# 0118-LEDz.net
KiCad netlist of a schematic drawn in EAGLE
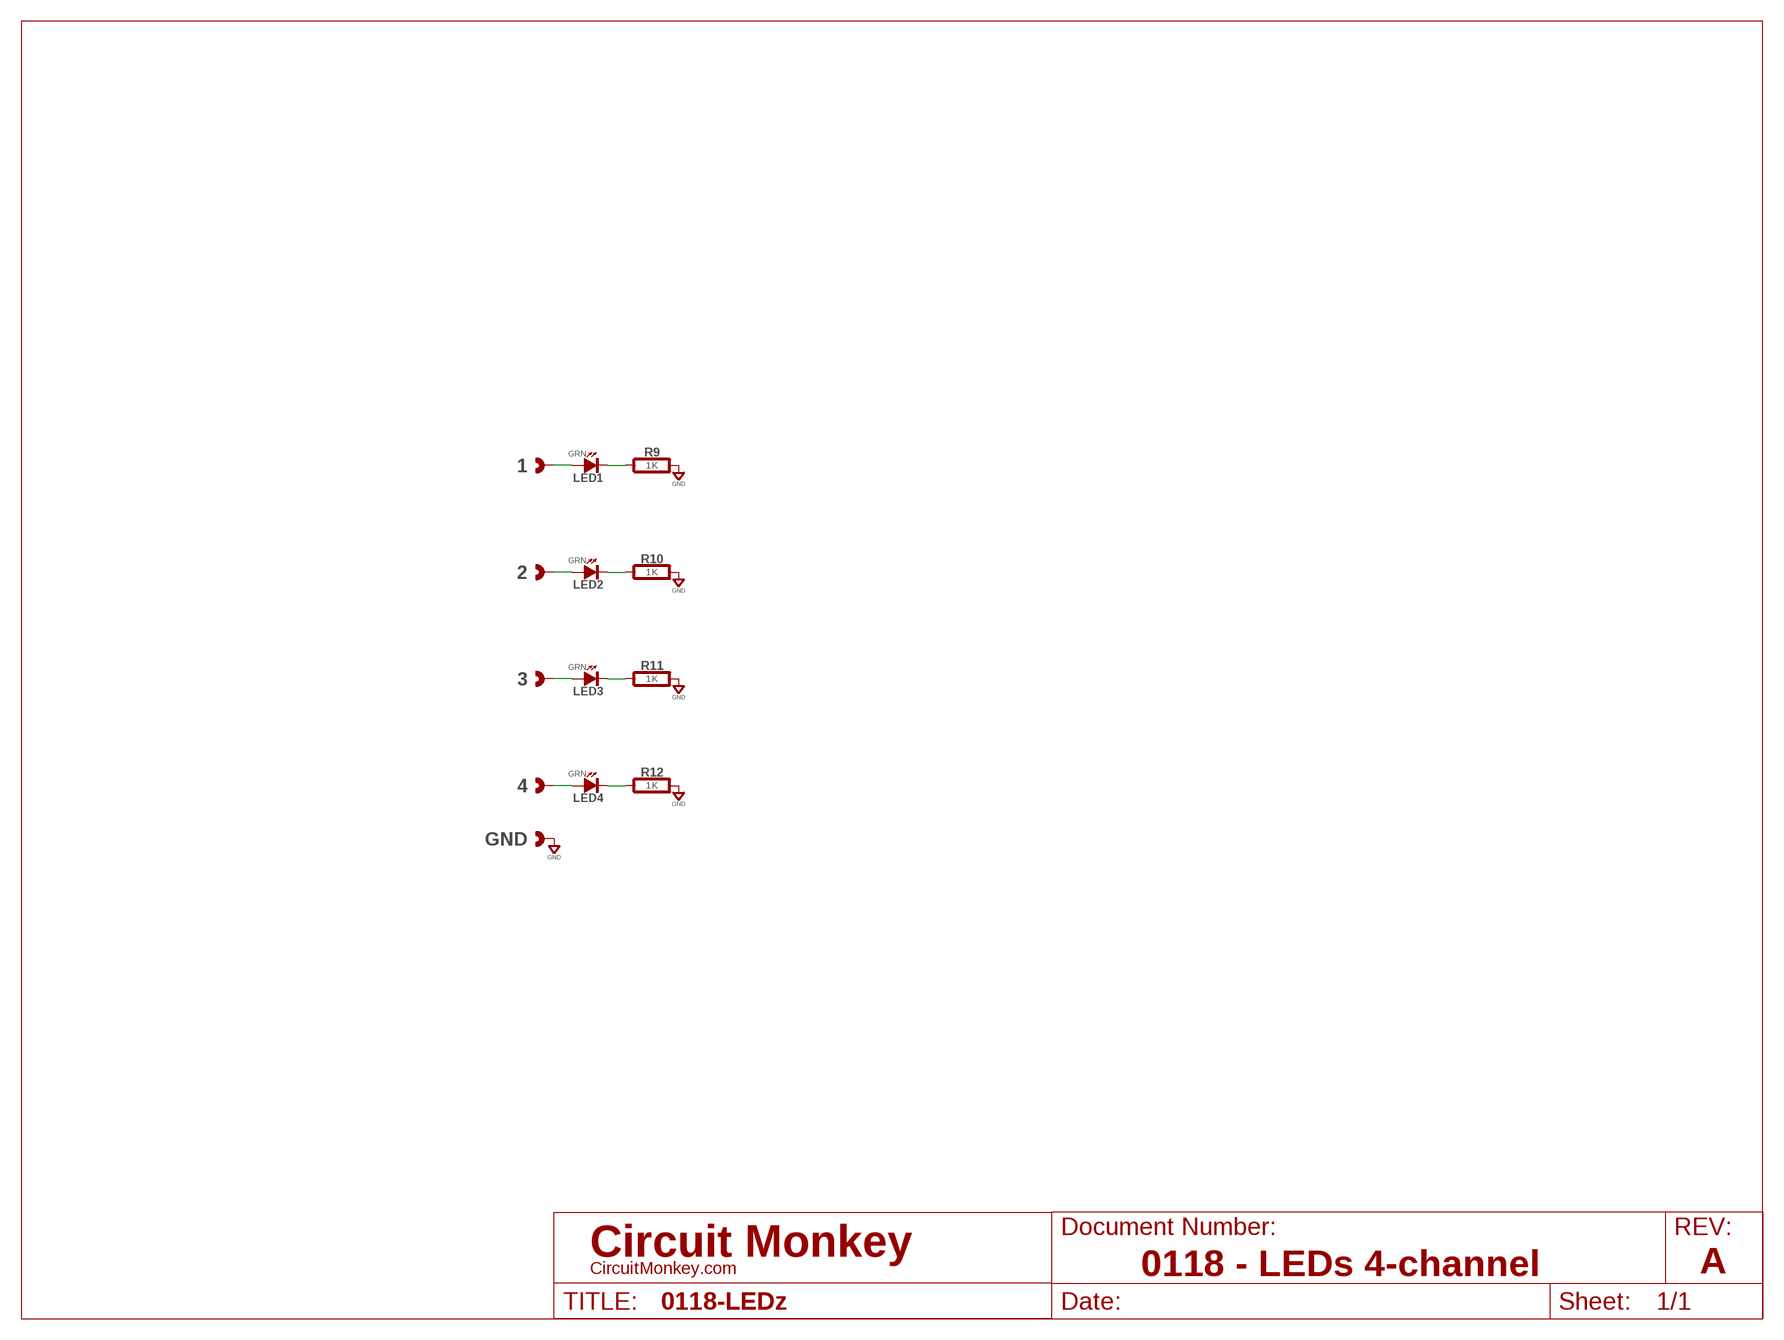
[diagram p0: schematic, sheet 1]

(export (version "E")
  (design (tool "Eeschema 10.0.6"))
  (components
    (comp (ref "1")
      (value "CAST-01X12.00MM")
      (footprint "eagle-import:CAST01-2.00MM")
      (libsource (lib "eagle-import") (part "CAST-01X12.00MM"))
    )
    (comp (ref "2")
      (value "CAST-01X12.00MM")
      (footprint "eagle-import:CAST01-2.00MM")
      (libsource (lib "eagle-import") (part "CAST-01X12.00MM"))
    )
    (comp (ref "3")
      (value "CAST-01X12.00MM")
      (footprint "eagle-import:CAST01-2.00MM")
      (libsource (lib "eagle-import") (part "CAST-01X12.00MM"))
    )
    (comp (ref "4")
      (value "CAST-01X12.00MM")
      (footprint "eagle-import:CAST01-2.00MM")
      (libsource (lib "eagle-import") (part "CAST-01X12.00MM"))
    )
    (comp (ref "GND")
      (value "CAST-01X12.00MM")
      (footprint "eagle-import:CAST01-2.00MM")
      (libsource (lib "eagle-import") (part "CAST-01X12.00MM"))
    )
    (comp (ref "LED1")
      (value "GRN")
      (footprint "eagle-import:SMD_0603")
      (libsource (lib "eagle-import") (part "SMT0603"))
    )
    (comp (ref "LED2")
      (value "GRN")
      (footprint "eagle-import:SMD_0603")
      (libsource (lib "eagle-import") (part "SMT0603"))
    )
    (comp (ref "LED3")
      (value "GRN")
      (footprint "eagle-import:SMD_0603")
      (libsource (lib "eagle-import") (part "SMT0603"))
    )
    (comp (ref "LED4")
      (value "GRN")
      (footprint "eagle-import:SMD_0603")
      (libsource (lib "eagle-import") (part "SMT0603"))
    )
    (comp (ref "R9")
      (value "1K")
      (footprint "eagle-import:0603-RES")
      (libsource (lib "eagle-import") (part "RESISTOR0603"))
    )
    (comp (ref "R10")
      (value "1K")
      (footprint "eagle-import:0603-RES")
      (libsource (lib "eagle-import") (part "RESISTOR0603"))
    )
    (comp (ref "R11")
      (value "1K")
      (footprint "eagle-import:0603-RES")
      (libsource (lib "eagle-import") (part "RESISTOR0603"))
    )
    (comp (ref "R12")
      (value "1K")
      (footprint "eagle-import:0603-RES")
      (libsource (lib "eagle-import") (part "RESISTOR0603"))
    )
  )
  (nets
    (net (code "1") (name "GND") (class "Default")
      (node (ref "GND") (pin "1") (pinfunction "1_1") (pintype "bidirectional"))
      (node (ref "GND") (pin "P$1") (pinfunction "1_P$1") (pintype "bidirectional"))
      (node (ref "GND") (pin "P$2") (pinfunction "1_P$2") (pintype "bidirectional"))
      (node (ref "R10") (pin "2") (pinfunction "2_2") (pintype "passive"))
      (node (ref "R11") (pin "2") (pinfunction "2_2") (pintype "passive"))
      (node (ref "R12") (pin "2") (pinfunction "2_2") (pintype "passive"))
      (node (ref "R9") (pin "2") (pinfunction "2_2") (pintype "passive"))
    )
    (net (code "2") (name "Net-(1-1-PadP$1)") (class "Default")
      (node (ref "1") (pin "1") (pinfunction "1_1") (pintype "bidirectional"))
      (node (ref "1") (pin "P$1") (pinfunction "1_P$1") (pintype "bidirectional"))
      (node (ref "1") (pin "P$2") (pinfunction "1_P$2") (pintype "bidirectional"))
      (node (ref "LED1") (pin "A") (pinfunction "A_A") (pintype "passive"))
    )
    (net (code "3") (name "Net-(2-1-PadP$1)") (class "Default")
      (node (ref "2") (pin "1") (pinfunction "1_1") (pintype "bidirectional"))
      (node (ref "2") (pin "P$1") (pinfunction "1_P$1") (pintype "bidirectional"))
      (node (ref "2") (pin "P$2") (pinfunction "1_P$2") (pintype "bidirectional"))
      (node (ref "LED2") (pin "A") (pinfunction "A_A") (pintype "passive"))
    )
    (net (code "4") (name "Net-(3-1-PadP$1)") (class "Default")
      (node (ref "3") (pin "1") (pinfunction "1_1") (pintype "bidirectional"))
      (node (ref "3") (pin "P$1") (pinfunction "1_P$1") (pintype "bidirectional"))
      (node (ref "3") (pin "P$2") (pinfunction "1_P$2") (pintype "bidirectional"))
      (node (ref "LED3") (pin "A") (pinfunction "A_A") (pintype "passive"))
    )
    (net (code "5") (name "Net-(4-1-PadP$1)") (class "Default")
      (node (ref "4") (pin "1") (pinfunction "1_1") (pintype "bidirectional"))
      (node (ref "4") (pin "P$1") (pinfunction "1_P$1") (pintype "bidirectional"))
      (node (ref "4") (pin "P$2") (pinfunction "1_P$2") (pintype "bidirectional"))
      (node (ref "LED4") (pin "A") (pinfunction "A_A") (pintype "passive"))
    )
    (net (code "6") (name "Net-(LED1-C)") (class "Default")
      (node (ref "LED1") (pin "K") (pinfunction "C_K") (pintype "passive"))
      (node (ref "R9") (pin "1") (pinfunction "1_1") (pintype "passive"))
    )
    (net (code "7") (name "Net-(LED2-C)") (class "Default")
      (node (ref "LED2") (pin "K") (pinfunction "C_K") (pintype "passive"))
      (node (ref "R10") (pin "1") (pinfunction "1_1") (pintype "passive"))
    )
    (net (code "8") (name "Net-(LED3-C)") (class "Default")
      (node (ref "LED3") (pin "K") (pinfunction "C_K") (pintype "passive"))
      (node (ref "R11") (pin "1") (pinfunction "1_1") (pintype "passive"))
    )
    (net (code "9") (name "Net-(LED4-C)") (class "Default")
      (node (ref "LED4") (pin "K") (pinfunction "C_K") (pintype "passive"))
      (node (ref "R12") (pin "1") (pinfunction "1_1") (pintype "passive"))
    )
  )
)
